# VC8Evrs3.net
KiCad netlist of a schematic drawn in EAGLE
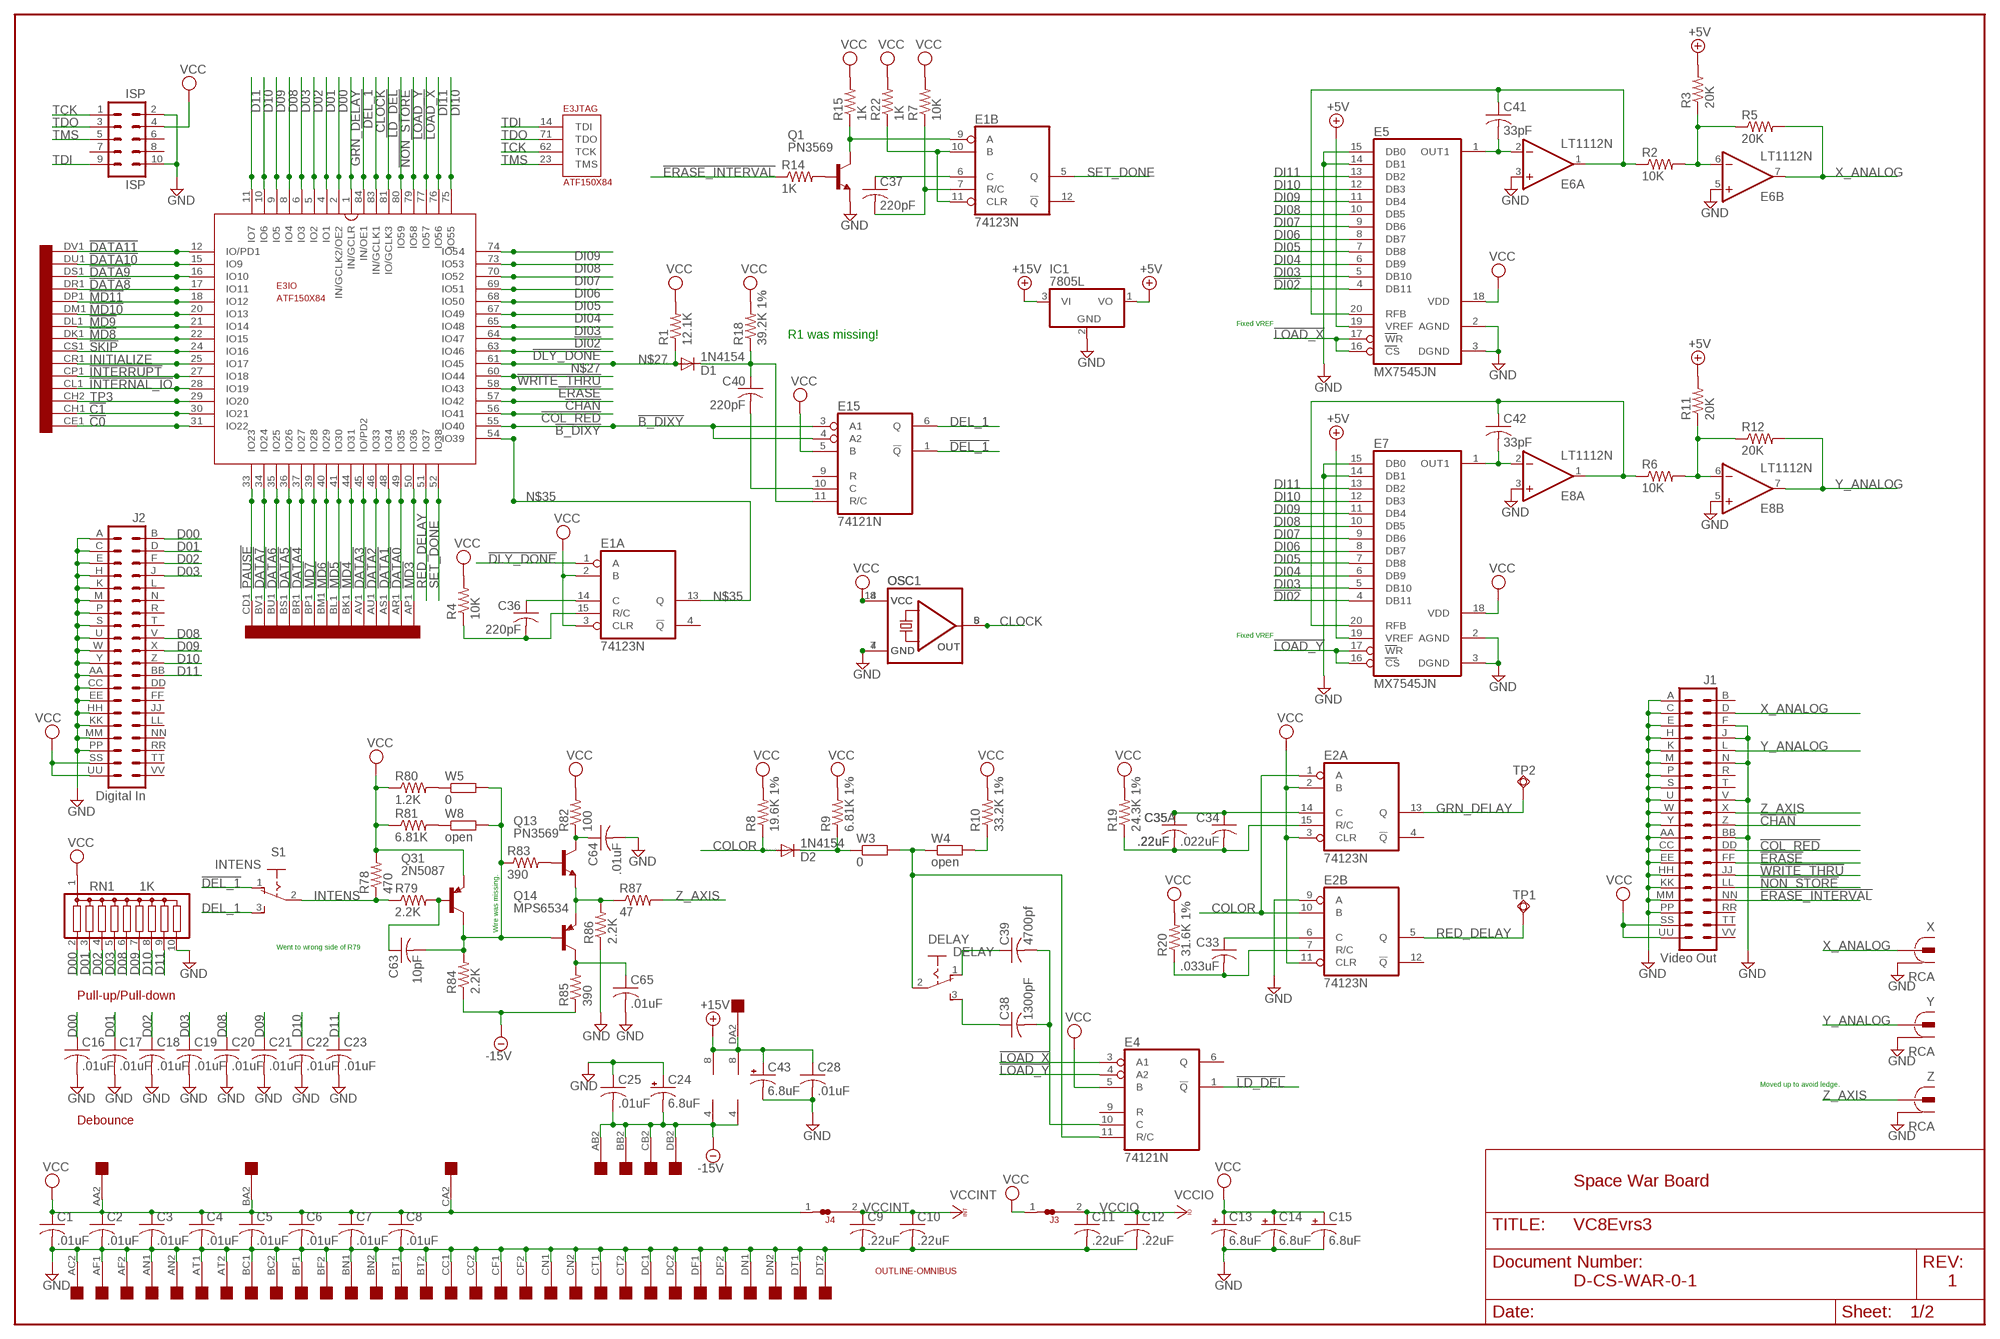
[diagram p0: schematic, sheet 1]

(export (version "E")
  (design (tool "Eeschema 10.0.6"))
  (components
    (comp (ref "C1")
      (value ".01uF")
      (footprint "eagle-import:C063-025X075")
      (libsource (lib "eagle-import") (part "C-US"))
    )
    (comp (ref "C2")
      (value ".01uF")
      (footprint "eagle-import:C063-025X075")
      (libsource (lib "eagle-import") (part "C-US"))
    )
    (comp (ref "C3")
      (value ".01uF")
      (footprint "eagle-import:C063-025X075")
      (libsource (lib "eagle-import") (part "C-US"))
    )
    (comp (ref "C4")
      (value ".01uF")
      (footprint "eagle-import:C063-025X075")
      (libsource (lib "eagle-import") (part "C-US"))
    )
    (comp (ref "C5")
      (value ".01uF")
      (footprint "eagle-import:C063-025X075")
      (libsource (lib "eagle-import") (part "C-US"))
    )
    (comp (ref "C6")
      (value ".01uF")
      (footprint "eagle-import:C063-025X075")
      (libsource (lib "eagle-import") (part "C-US"))
    )
    (comp (ref "C7")
      (value ".01uF")
      (footprint "eagle-import:C063-025X075")
      (libsource (lib "eagle-import") (part "C-US"))
    )
    (comp (ref "C8")
      (value ".01uF")
      (footprint "eagle-import:C063-025X075")
      (libsource (lib "eagle-import") (part "C-US"))
    )
    (comp (ref "C9")
      (value ".22uF")
      (footprint "eagle-import:C063-025X075")
      (libsource (lib "eagle-import") (part "C-US"))
    )
    (comp (ref "C10")
      (value ".22uF")
      (footprint "eagle-import:C063-025X075")
      (libsource (lib "eagle-import") (part "C-US"))
    )
    (comp (ref "C11")
      (value ".22uF")
      (footprint "eagle-import:C063-025X075")
      (libsource (lib "eagle-import") (part "C-US"))
    )
    (comp (ref "C12")
      (value ".22uF")
      (footprint "eagle-import:C063-025X075")
      (libsource (lib "eagle-import") (part "C-US"))
    )
    (comp (ref "C13")
      (value "6.8uF")
      (footprint "eagle-import:E12-8")
      (libsource (lib "eagle-import") (part "CPOL-USE20-8AXIAL"))
    )
    (comp (ref "C14")
      (value "6.8uF")
      (footprint "eagle-import:E12-8")
      (libsource (lib "eagle-import") (part "CPOL-USE20-8AXIAL"))
    )
    (comp (ref "C15")
      (value "6.8uF")
      (footprint "eagle-import:E12-8")
      (libsource (lib "eagle-import") (part "CPOL-USE20-8AXIAL"))
    )
    (comp (ref "C16")
      (value ".01uF")
      (footprint "eagle-import:C063-025X075")
      (libsource (lib "eagle-import") (part "C-US"))
    )
    (comp (ref "C17")
      (value ".01uF")
      (footprint "eagle-import:C063-025X075")
      (libsource (lib "eagle-import") (part "C-US"))
    )
    (comp (ref "C18")
      (value ".01uF")
      (footprint "eagle-import:C063-025X075")
      (libsource (lib "eagle-import") (part "C-US"))
    )
    (comp (ref "C19")
      (value ".01uF")
      (footprint "eagle-import:C063-025X075")
      (libsource (lib "eagle-import") (part "C-US"))
    )
    (comp (ref "C20")
      (value ".01uF")
      (footprint "eagle-import:C063-025X075")
      (libsource (lib "eagle-import") (part "C-US"))
    )
    (comp (ref "C21")
      (value ".01uF")
      (footprint "eagle-import:C063-025X075")
      (libsource (lib "eagle-import") (part "C-US"))
    )
    (comp (ref "C22")
      (value ".01uF")
      (footprint "eagle-import:C063-025X075")
      (libsource (lib "eagle-import") (part "C-US"))
    )
    (comp (ref "C23")
      (value ".01uF")
      (footprint "eagle-import:C063-025X075")
      (libsource (lib "eagle-import") (part "C-US"))
    )
    (comp (ref "C24")
      (value "6.8uF")
      (footprint "eagle-import:E12-8")
      (libsource (lib "eagle-import") (part "CPOL-USE20-8AXIAL"))
    )
    (comp (ref "C25")
      (value ".01uF")
      (footprint "eagle-import:C063-025X075")
      (libsource (lib "eagle-import") (part "C-US"))
    )
    (comp (ref "C28")
      (value ".01uF")
      (footprint "eagle-import:C063-025X075")
      (libsource (lib "eagle-import") (part "C-US"))
    )
    (comp (ref "C33")
      (value ".033uF")
      (footprint "eagle-import:C102-043X133")
      (libsource (lib "eagle-import") (part "C-US102-043X133"))
    )
    (comp (ref "C34")
      (value ".022uF")
      (footprint "eagle-import:C102-043X133")
      (libsource (lib "eagle-import") (part "C-US102-043X133"))
    )
    (comp (ref "C35")
      (value ".22uF")
      (footprint "eagle-import:C050-025X075")
      (libsource (lib "eagle-import") (part "C-US050-025X075"))
    )
    (comp (ref "C35A")
      (value ".22uF")
      (footprint "eagle-import:C102-043X133")
      (libsource (lib "eagle-import") (part "C-US102-043X133"))
    )
    (comp (ref "C36")
      (value "220pF")
      (footprint "eagle-import:C063-025X075")
      (libsource (lib "eagle-import") (part "C-US"))
    )
    (comp (ref "C37")
      (value "220pF")
      (footprint "eagle-import:C063-025X075")
      (libsource (lib "eagle-import") (part "C-US"))
    )
    (comp (ref "C38")
      (value "1300pF")
      (footprint "eagle-import:C150-054X183")
      (libsource (lib "eagle-import") (part "C-US150-054X183"))
    )
    (comp (ref "C39")
      (value "4700pf")
      (footprint "eagle-import:C102-043X133")
      (libsource (lib "eagle-import") (part "C-US102-043X133"))
    )
    (comp (ref "C40")
      (value "220pF")
      (footprint "eagle-import:C063-025X075")
      (libsource (lib "eagle-import") (part "C-US"))
    )
    (comp (ref "C41")
      (value "33pF")
      (footprint "eagle-import:C063-025X075")
      (libsource (lib "eagle-import") (part "C-US"))
    )
    (comp (ref "C42")
      (value "33pF")
      (footprint "eagle-import:C063-025X075")
      (libsource (lib "eagle-import") (part "C-US"))
    )
    (comp (ref "C43")
      (value "6.8uF")
      (footprint "eagle-import:E12-8")
      (libsource (lib "eagle-import") (part "CPOL-USE20-8AXIAL"))
    )
    (comp (ref "C63")
      (value "10pF")
      (footprint "eagle-import:C063-025X075")
      (libsource (lib "eagle-import") (part "C-US"))
    )
    (comp (ref "C64")
      (value ".01uF")
      (footprint "eagle-import:C063-025X075")
      (libsource (lib "eagle-import") (part "C-US"))
    )
    (comp (ref "C65")
      (value ".01uF")
      (footprint "eagle-import:C063-025X075")
      (libsource (lib "eagle-import") (part "C-US"))
    )
    (comp (ref "D1")
      (value "1N4154")
      (footprint "eagle-import:DO35-10")
      (libsource (lib "eagle-import") (part "DIODE-DO35-10"))
    )
    (comp (ref "D2")
      (value "1N4154")
      (footprint "eagle-import:DO35-10")
      (libsource (lib "eagle-import") (part "DIODE-DO35-10"))
    )
    (comp (ref "DELAY")
      (value "DELAY")
      (footprint "eagle-import:M251")
      (libsource (lib "eagle-import") (part "M251"))
    )
    (comp (ref "E1")
      (value "74123N")
      (footprint "eagle-import:DIL16")
      (libsource (lib "eagle-import") (part "74123N"))
    )
    (comp (ref "E2")
      (value "74123N")
      (footprint "eagle-import:DIL16")
      (libsource (lib "eagle-import") (part "74123N"))
    )
    (comp (ref "E3")
      (value "ATF150X84")
      (footprint "eagle-import:S84")
      (libsource (lib "eagle-import") (part "ATF150X84"))
    )
    (comp (ref "E4")
      (value "74121N")
      (footprint "eagle-import:DIL14")
      (libsource (lib "eagle-import") (part "74121N"))
    )
    (comp (ref "E5")
      (value "MX7545JN")
      (footprint "eagle-import:DIL20")
      (fields (field (name "MPN") "MX7545JN+"))
      (libsource (lib "eagle-import") (part "MX7545JN"))
    )
    (comp (ref "E6")
      (value "LT1112N")
      (footprint "eagle-import:DIL08")
      (libsource (lib "eagle-import") (part "1458NLM"))
    )
    (comp (ref "E7")
      (value "MX7545JN")
      (footprint "eagle-import:DIL20")
      (fields (field (name "MPN") "MX7545JN+"))
      (libsource (lib "eagle-import") (part "MX7545JN"))
    )
    (comp (ref "E8")
      (value "LT1112N")
      (footprint "eagle-import:DIL08")
      (libsource (lib "eagle-import") (part "1458NLM"))
    )
    (comp (ref "E15")
      (value "74121N")
      (footprint "eagle-import:DIL14")
      (libsource (lib "eagle-import") (part "74121N"))
    )
    (comp (ref "IC1")
      (value "7805L")
      (footprint "eagle-import:TO92")
      (libsource (lib "eagle-import") (part "78L05"))
    )
    (comp (ref "ISP")
      (value "ISP")
      (footprint "eagle-import:ML10")
      (libsource (lib "eagle-import") (part "ML10"))
    )
    (comp (ref "J1")
      (value "Video Out")
      (footprint "eagle-import:DEC40PINH")
      (libsource (lib "eagle-import") (part "DEC40PINH"))
    )
    (comp (ref "J2")
      (value "Digital In")
      (footprint "eagle-import:DEC40PINH")
      (libsource (lib "eagle-import") (part "DEC40PINH"))
    )
    (comp (ref "J3")
      (value "JUMPER-NC1")
      (footprint "eagle-import:NC1")
      (libsource (lib "eagle-import") (part "JUMPER-NC1"))
    )
    (comp (ref "J4")
      (value "JUMPER-NC1")
      (footprint "eagle-import:NC1")
      (libsource (lib "eagle-import") (part "JUMPER-NC1"))
    )
    (comp (ref "OMNIBUS")
      (value "QUAD")
      (footprint "eagle-import:EDGE-CON8")
      (libsource (lib "eagle-import") (part "QUAD"))
    )
    (comp (ref "OSC")
      (value "QG5460")
      (footprint "eagle-import:DIL08S")
      (libsource (lib "eagle-import") (part "QG5460"))
    )
    (comp (ref "OSC1")
      (value "QG5860")
      (footprint "eagle-import:DIL14S")
      (libsource (lib "eagle-import") (part "QG5860"))
    )
    (comp (ref "Q1")
      (value "PN3569")
      (footprint "eagle-import:TO5")
      (libsource (lib "eagle-import") (part "-NPN-TO5"))
    )
    (comp (ref "Q13")
      (value "PN3569")
      (footprint "eagle-import:TO5")
      (libsource (lib "eagle-import") (part "-NPN-TO5"))
    )
    (comp (ref "Q14")
      (value "MPS6534")
      (footprint "eagle-import:TO5")
      (libsource (lib "eagle-import") (part "-PNP-TO5"))
    )
    (comp (ref "Q31")
      (value "2N5087")
      (footprint "eagle-import:TO5")
      (libsource (lib "eagle-import") (part "-PNP-TO5"))
    )
    (comp (ref "R1")
      (value "12.1K")
      (footprint "eagle-import:0207_15")
      (libsource (lib "eagle-import") (part "R-US_0207/15"))
    )
    (comp (ref "R2")
      (value "10K")
      (footprint "eagle-import:0207_10")
      (libsource (lib "eagle-import") (part "R-US_0207/10"))
    )
    (comp (ref "R3")
      (value "20K")
      (footprint "eagle-import:0207_10")
      (libsource (lib "eagle-import") (part "R-US_0207/10"))
    )
    (comp (ref "R4")
      (value "10K")
      (footprint "eagle-import:0207_10")
      (libsource (lib "eagle-import") (part "R-US_0207/10"))
    )
    (comp (ref "R5")
      (value "20K")
      (footprint "eagle-import:0207_10")
      (libsource (lib "eagle-import") (part "R-US_0207/10"))
    )
    (comp (ref "R6")
      (value "10K")
      (footprint "eagle-import:0207_10")
      (libsource (lib "eagle-import") (part "R-US_0207/10"))
    )
    (comp (ref "R7")
      (value "10K")
      (footprint "eagle-import:0207_10")
      (libsource (lib "eagle-import") (part "R-US_0207/10"))
    )
    (comp (ref "R8")
      (value "19.6K 1%")
      (footprint "eagle-import:0207_15")
      (libsource (lib "eagle-import") (part "R-US_0207/15"))
    )
    (comp (ref "R9")
      (value "6.81K 1%")
      (footprint "eagle-import:0207_15")
      (libsource (lib "eagle-import") (part "R-US_0207/15"))
    )
    (comp (ref "R10")
      (value "33.2K 1%")
      (footprint "eagle-import:0207_15")
      (libsource (lib "eagle-import") (part "R-US_0207/15"))
    )
    (comp (ref "R11")
      (value "20K")
      (footprint "eagle-import:0207_10")
      (libsource (lib "eagle-import") (part "R-US_0207/10"))
    )
    (comp (ref "R12")
      (value "20K")
      (footprint "eagle-import:0207_10")
      (libsource (lib "eagle-import") (part "R-US_0207/10"))
    )
    (comp (ref "R14")
      (value "1K")
      (footprint "eagle-import:0207_10")
      (libsource (lib "eagle-import") (part "R-US_0207/10"))
    )
    (comp (ref "R15")
      (value "1K")
      (footprint "eagle-import:0207_10")
      (libsource (lib "eagle-import") (part "R-US_0207/10"))
    )
    (comp (ref "R18")
      (value "39.2K 1%")
      (footprint "eagle-import:0207_15")
      (libsource (lib "eagle-import") (part "R-US_0207/15"))
    )
    (comp (ref "R19")
      (value "24.3K 1%")
      (footprint "eagle-import:0207_15")
      (libsource (lib "eagle-import") (part "R-US_0207/15"))
    )
    (comp (ref "R20")
      (value "31.6K 1%")
      (footprint "eagle-import:0207_15")
      (libsource (lib "eagle-import") (part "R-US_0207/15"))
    )
    (comp (ref "R22")
      (value "1K")
      (footprint "eagle-import:0207_10")
      (libsource (lib "eagle-import") (part "R-US_0207/10"))
    )
    (comp (ref "R78")
      (value "470")
      (footprint "eagle-import:0207_10")
      (libsource (lib "eagle-import") (part "R-US_0207/10"))
    )
    (comp (ref "R79")
      (value "2.2K")
      (footprint "eagle-import:0207_10")
      (libsource (lib "eagle-import") (part "R-US_0207/10"))
    )
    (comp (ref "R80")
      (value "1.2K")
      (footprint "eagle-import:0207_10")
      (libsource (lib "eagle-import") (part "R-US_0207/10"))
    )
    (comp (ref "R81")
      (value "6.81K")
      (footprint "eagle-import:0207_10")
      (libsource (lib "eagle-import") (part "R-US_0207/10"))
    )
    (comp (ref "R82")
      (value "100")
      (footprint "eagle-import:0207_10")
      (libsource (lib "eagle-import") (part "R-US_0207/10"))
    )
    (comp (ref "R83")
      (value "390")
      (footprint "eagle-import:0207_10")
      (libsource (lib "eagle-import") (part "R-US_0207/10"))
    )
    (comp (ref "R84")
      (value "2.2K")
      (footprint "eagle-import:0207_10")
      (libsource (lib "eagle-import") (part "R-US_0207/10"))
    )
    (comp (ref "R85")
      (value "390")
      (footprint "eagle-import:0207_10")
      (libsource (lib "eagle-import") (part "R-US_0207/10"))
    )
    (comp (ref "R86")
      (value "2.2K")
      (footprint "eagle-import:0207_10")
      (libsource (lib "eagle-import") (part "R-US_0207/10"))
    )
    (comp (ref "R87")
      (value "47")
      (footprint "eagle-import:0207_10")
      (libsource (lib "eagle-import") (part "R-US_0207/10"))
    )
    (comp (ref "RN1")
      (value "1K")
      (footprint "eagle-import:SIL10")
      (libsource (lib "eagle-import") (part "G09R"))
    )
    (comp (ref "S1")
      (value "INTENS")
      (footprint "eagle-import:M251")
      (libsource (lib "eagle-import") (part "M251"))
    )
    (comp (ref "TP1")
      (value "TPSQPAD1-17")
      (footprint "eagle-import:P1-17")
      (libsource (lib "eagle-import") (part "TPSQPAD1-17"))
    )
    (comp (ref "TP2")
      (value "TPSQPAD1-17")
      (footprint "eagle-import:P1-17")
      (libsource (lib "eagle-import") (part "TPSQPAD1-17"))
    )
    (comp (ref "U$1")
      (value "OUTLINE-OMNIBUS")
      (footprint "eagle-import:OMNIBUS")
      (libsource (lib "eagle-import") (part "OUTLINE-OMNIBUS"))
    )
    (comp (ref "W3")
      (value "0")
      (footprint "eagle-import:0207_10")
      (libsource (lib "eagle-import") (part "R-EU_0207/10"))
    )
    (comp (ref "W4")
      (value "open")
      (footprint "eagle-import:0207_10")
      (libsource (lib "eagle-import") (part "R-EU_0207/10"))
    )
    (comp (ref "W5")
      (value "0")
      (footprint "eagle-import:0207_10")
      (libsource (lib "eagle-import") (part "R-EU_0207/10"))
    )
    (comp (ref "W8")
      (value "open")
      (footprint "eagle-import:0207_10")
      (libsource (lib "eagle-import") (part "R-EU_0207/10"))
    )
    (comp (ref "X")
      (value "RCA")
      (footprint "eagle-import:RCA")
      (libsource (lib "eagle-import") (part "RCA"))
    )
    (comp (ref "Y")
      (value "RCA")
      (footprint "eagle-import:RCA")
      (libsource (lib "eagle-import") (part "RCA"))
    )
    (comp (ref "Z")
      (value "RCA")
      (footprint "eagle-import:RCA")
      (libsource (lib "eagle-import") (part "RCA"))
    )
  )
  (nets
    (net (code "1") (name "+5V") (class "Default")
      (node (ref "E5") (pin "19") (pinfunction "VREF_19") (pintype "input"))
      (node (ref "E7") (pin "19") (pinfunction "VREF_19") (pintype "input"))
      (node (ref "IC1") (pin "1") (pinfunction "VO_1") (pintype "passive"))
      (node (ref "R11") (pin "2") (pinfunction "2_2") (pintype "passive"))
      (node (ref "R3") (pin "2") (pinfunction "2_2") (pintype "passive"))
    )
    (net (code "2") (name "+15V") (class "Default")
      (node (ref "C28") (pin "1") (pinfunction "1_1") (pintype "passive"))
      (node (ref "C43") (pin "+") (pinfunction "+_+") (pintype "passive"))
      (node (ref "E6") (pin "8") (pinfunction "V+_8") (pintype "power_in"))
      (node (ref "E8") (pin "8") (pinfunction "V+_8") (pintype "power_in"))
      (node (ref "IC1") (pin "3") (pinfunction "VI_3") (pintype "input"))
      (node (ref "OMNIBUS") (pin "DA2") (pinfunction "1_DA2") (pintype "bidirectional"))
    )
    (net (code "3") (name "-15V") (class "Default")
      (node (ref "C24") (pin "-") (pinfunction "-_-") (pintype "passive"))
      (node (ref "C25") (pin "2") (pinfunction "2_2") (pintype "passive"))
      (node (ref "E6") (pin "4") (pinfunction "V-_4") (pintype "power_in"))
      (node (ref "E8") (pin "4") (pinfunction "V-_4") (pintype "power_in"))
      (node (ref "OMNIBUS") (pin "AB2") (pinfunction "1_AB2") (pintype "bidirectional"))
      (node (ref "OMNIBUS") (pin "BB2") (pinfunction "1_BB2") (pintype "bidirectional"))
      (node (ref "OMNIBUS") (pin "CB2") (pinfunction "1_CB2") (pintype "bidirectional"))
      (node (ref "OMNIBUS") (pin "DB2") (pinfunction "1_DB2") (pintype "bidirectional"))
      (node (ref "R84") (pin "1") (pinfunction "1_1") (pintype "passive"))
      (node (ref "R85") (pin "1") (pinfunction "1_1") (pintype "passive"))
    )
    (net (code "4") (name "CLOCK") (class "Default")
      (node (ref "E3") (pin "83") (pinfunction "IN/GCLK1_83") (pintype "input"))
      (node (ref "OSC") (pin "5") (pinfunction "OUT_5") (pintype "output"))
      (node (ref "OSC1") (pin "8") (pinfunction "OUT_8") (pintype "output"))
    )
    (net (code "5") (name "COLOR") (class "Default")
      (node (ref "D2") (pin "A") (pinfunction "A_A") (pintype "passive"))
      (node (ref "E2") (pin "1") (pinfunction "A_1") (pintype "input"))
      (node (ref "E2") (pin "10") (pinfunction "B_10") (pintype "input"))
      (node (ref "R8") (pin "1") (pinfunction "1_1") (pintype "passive"))
    )
    (net (code "6") (name "D00") (class "Default")
      (node (ref "C16") (pin "1") (pinfunction "1_1") (pintype "passive"))
      (node (ref "E3") (pin "2") (pinfunction "IN/GCLK2/OE2_2") (pintype "input"))
      (node (ref "J2") (pin "B") (pinfunction "2_B") (pintype "bidirectional"))
      (node (ref "RN1") (pin "2") (pinfunction "2_2") (pintype "passive"))
    )
    (net (code "7") (name "D01") (class "Default")
      (node (ref "C17") (pin "1") (pinfunction "1_1") (pintype "passive"))
      (node (ref "E3") (pin "4") (pinfunction "IO1_4") (pintype "bidirectional"))
      (node (ref "J2") (pin "D") (pinfunction "4_D") (pintype "bidirectional"))
      (node (ref "RN1") (pin "3") (pinfunction "3_3") (pintype "passive"))
    )
    (net (code "8") (name "D02") (class "Default")
      (node (ref "C18") (pin "1") (pinfunction "1_1") (pintype "passive"))
      (node (ref "E3") (pin "5") (pinfunction "IO2_5") (pintype "bidirectional"))
      (node (ref "J2") (pin "F") (pinfunction "6_F") (pintype "bidirectional"))
      (node (ref "RN1") (pin "4") (pinfunction "4_4") (pintype "passive"))
    )
    (net (code "9") (name "D03") (class "Default")
      (node (ref "C19") (pin "1") (pinfunction "1_1") (pintype "passive"))
      (node (ref "E3") (pin "6") (pinfunction "IO3_6") (pintype "bidirectional"))
      (node (ref "J2") (pin "J") (pinfunction "8_J") (pintype "bidirectional"))
      (node (ref "RN1") (pin "5") (pinfunction "5_5") (pintype "passive"))
    )
    (net (code "10") (name "D08") (class "Default")
      (node (ref "C20") (pin "1") (pinfunction "1_1") (pintype "passive"))
      (node (ref "E3") (pin "8") (pinfunction "IO4_8") (pintype "bidirectional"))
      (node (ref "J2") (pin "V") (pinfunction "18_V") (pintype "bidirectional"))
      (node (ref "RN1") (pin "6") (pinfunction "6_6") (pintype "passive"))
    )
    (net (code "11") (name "D09") (class "Default")
      (node (ref "C21") (pin "1") (pinfunction "1_1") (pintype "passive"))
      (node (ref "E3") (pin "9") (pinfunction "IO5_9") (pintype "bidirectional"))
      (node (ref "J2") (pin "X") (pinfunction "20_X") (pintype "bidirectional"))
      (node (ref "RN1") (pin "7") (pinfunction "7_7") (pintype "passive"))
    )
    (net (code "12") (name "D10") (class "Default")
      (node (ref "C22") (pin "1") (pinfunction "1_1") (pintype "passive"))
      (node (ref "E3") (pin "10") (pinfunction "IO6_10") (pintype "bidirectional"))
      (node (ref "J2") (pin "Z") (pinfunction "22_Z") (pintype "bidirectional"))
      (node (ref "RN1") (pin "8") (pinfunction "8_8") (pintype "passive"))
    )
    (net (code "13") (name "D11") (class "Default")
      (node (ref "C23") (pin "1") (pinfunction "1_1") (pintype "passive"))
      (node (ref "E3") (pin "11") (pinfunction "IO7_11") (pintype "bidirectional"))
      (node (ref "J2") (pin "BB") (pinfunction "24_BB") (pintype "bidirectional"))
      (node (ref "RN1") (pin "9") (pinfunction "9_9") (pintype "passive"))
    )
    (net (code "14") (name "DEL_1") (class "Default")
      (node (ref "E15") (pin "6") (pinfunction "Q_6") (pintype "output"))
      (node (ref "S1") (pin "3") (pinfunction "S_3") (pintype "passive"))
    )
    (net (code "15") (name "DI03") (class "Default")
      (node (ref "E3") (pin "65") (pinfunction "IO48_65") (pintype "bidirectional"))
      (node (ref "E5") (pin "5") (pinfunction "DB10_5") (pintype "input"))
      (node (ref "E7") (pin "5") (pinfunction "DB10_5") (pintype "input"))
    )
    (net (code "16") (name "DI04") (class "Default")
      (node (ref "E3") (pin "67") (pinfunction "IO49_67") (pintype "bidirectional"))
      (node (ref "E5") (pin "6") (pinfunction "DB9_6") (pintype "input"))
      (node (ref "E7") (pin "6") (pinfunction "DB9_6") (pintype "input"))
    )
    (net (code "17") (name "DI05") (class "Default")
      (node (ref "E3") (pin "68") (pinfunction "IO50_68") (pintype "bidirectional"))
      (node (ref "E5") (pin "7") (pinfunction "DB8_7") (pintype "input"))
      (node (ref "E7") (pin "7") (pinfunction "DB8_7") (pintype "input"))
    )
    (net (code "18") (name "DI06") (class "Default")
      (node (ref "E3") (pin "69") (pinfunction "IO51_69") (pintype "bidirectional"))
      (node (ref "E5") (pin "8") (pinfunction "DB7_8") (pintype "input"))
      (node (ref "E7") (pin "8") (pinfunction "DB7_8") (pintype "input"))
    )
    (net (code "19") (name "DI07") (class "Default")
      (node (ref "E3") (pin "70") (pinfunction "IO52_70") (pintype "bidirectional"))
      (node (ref "E5") (pin "9") (pinfunction "DB6_9") (pintype "input"))
      (node (ref "E7") (pin "9") (pinfunction "DB6_9") (pintype "input"))
    )
    (net (code "20") (name "DI08") (class "Default")
      (node (ref "E3") (pin "73") (pinfunction "IO53_73") (pintype "bidirectional"))
      (node (ref "E5") (pin "10") (pinfunction "DB5_10") (pintype "input"))
      (node (ref "E7") (pin "10") (pinfunction "DB5_10") (pintype "input"))
    )
    (net (code "21") (name "DI09") (class "Default")
      (node (ref "E3") (pin "74") (pinfunction "IO54_74") (pintype "bidirectional"))
      (node (ref "E5") (pin "11") (pinfunction "DB4_11") (pintype "input"))
      (node (ref "E7") (pin "11") (pinfunction "DB4_11") (pintype "input"))
    )
    (net (code "22") (name "DI10") (class "Default")
      (node (ref "E3") (pin "75") (pinfunction "IO55_75") (pintype "bidirectional"))
      (node (ref "E5") (pin "12") (pinfunction "DB3_12") (pintype "input"))
      (node (ref "E7") (pin "12") (pinfunction "DB3_12") (pintype "input"))
    )
    (net (code "23") (name "DI11") (class "Default")
      (node (ref "E3") (pin "76") (pinfunction "IO56_76") (pintype "bidirectional"))
      (node (ref "E5") (pin "13") (pinfunction "DB2_13") (pintype "input"))
      (node (ref "E7") (pin "13") (pinfunction "DB2_13") (pintype "input"))
    )
    (net (code "24") (name "GND") (class "Default")
      (node (ref "C1") (pin "2") (pinfunction "2_2") (pintype "passive"))
      (node (ref "C10") (pin "2") (pinfunction "2_2") (pintype "passive"))
      (node (ref "C11") (pin "2") (pinfunction "2_2") (pintype "passive"))
      (node (ref "C12") (pin "2") (pinfunction "2_2") (pintype "passive"))
      (node (ref "C13") (pin "-") (pinfunction "-_-") (pintype "passive"))
      (node (ref "C14") (pin "-") (pinfunction "-_-") (pintype "passive"))
      (node (ref "C15") (pin "-") (pinfunction "-_-") (pintype "passive"))
      (node (ref "C16") (pin "2") (pinfunction "2_2") (pintype "passive"))
      (node (ref "C17") (pin "2") (pinfunction "2_2") (pintype "passive"))
      (node (ref "C18") (pin "2") (pinfunction "2_2") (pintype "passive"))
      (node (ref "C19") (pin "2") (pinfunction "2_2") (pintype "passive"))
      (node (ref "C2") (pin "2") (pinfunction "2_2") (pintype "passive"))
      (node (ref "C20") (pin "2") (pinfunction "2_2") (pintype "passive"))
      (node (ref "C21") (pin "2") (pinfunction "2_2") (pintype "passive"))
      (node (ref "C22") (pin "2") (pinfunction "2_2") (pintype "passive"))
      (node (ref "C23") (pin "2") (pinfunction "2_2") (pintype "passive"))
      (node (ref "C24") (pin "+") (pinfunction "+_+") (pintype "passive"))
      (node (ref "C25") (pin "1") (pinfunction "1_1") (pintype "passive"))
      (node (ref "C28") (pin "2") (pinfunction "2_2") (pintype "passive"))
      (node (ref "C3") (pin "2") (pinfunction "2_2") (pintype "passive"))
      (node (ref "C4") (pin "2") (pinfunction "2_2") (pintype "passive"))
      (node (ref "C43") (pin "-") (pinfunction "-_-") (pintype "passive"))
      (node (ref "C5") (pin "2") (pinfunction "2_2") (pintype "passive"))
      (node (ref "C6") (pin "2") (pinfunction "2_2") (pintype "passive"))
      (node (ref "C64") (pin "2") (pinfunction "2_2") (pintype "passive"))
      (node (ref "C65") (pin "2") (pinfunction "2_2") (pintype "passive"))
      (node (ref "C7") (pin "2") (pinfunction "2_2") (pintype "passive"))
      (node (ref "C8") (pin "2") (pinfunction "2_2") (pintype "passive"))
      (node (ref "C9") (pin "2") (pinfunction "2_2") (pintype "passive"))
      (node (ref "E2") (pin "9") (pinfunction "A_9") (pintype "input"))
      (node (ref "E5") (pin "14") (pinfunction "DB1_14") (pintype "input"))
      (node (ref "E5") (pin "15") (pinfunction "DB0_15") (pintype "input"))
      (node (ref "E5") (pin "2") (pinfunction "AGND_2") (pintype "power_in"))
      (node (ref "E5") (pin "3") (pinfunction "DGND_3") (pintype "power_in"))
      (node (ref "E6") (pin "3") (pinfunction "+IN_3") (pintype "input"))
      (node (ref "E6") (pin "5") (pinfunction "+IN_5") (pintype "input"))
      (node (ref "E7") (pin "14") (pinfunction "DB1_14") (pintype "input"))
      (node (ref "E7") (pin "15") (pinfunction "DB0_15") (pintype "input"))
      (node (ref "E7") (pin "2") (pinfunction "AGND_2") (pintype "power_in"))
      (node (ref "E7") (pin "3") (pinfunction "DGND_3") (pintype "power_in"))
      (node (ref "E8") (pin "3") (pinfunction "+IN_3") (pintype "input"))
      (node (ref "E8") (pin "5") (pinfunction "+IN_5") (pintype "input"))
      (node (ref "IC1") (pin "2") (pinfunction "GND_2") (pintype "passive"))
      (node (ref "ISP") (pin "10") (pinfunction "10_10") (pintype "passive"))
      (node (ref "ISP") (pin "2") (pinfunction "2_2") (pintype "passive"))
      (node (ref "J1") (pin "A") (pinfunction "1_A") (pintype "bidirectional"))
      (node (ref "J1") (pin "AA") (pinfunction "23_AA") (pintype "bidirectional"))
      (node (ref "J1") (pin "BB") (pinfunction "24_BB") (pintype "bidirectional"))
      (node (ref "J1") (pin "C") (pinfunction "3_C") (pintype "bidirectional"))
      (node (ref "J1") (pin "CC") (pinfunction "25_CC") (pintype "bidirectional"))
      (node (ref "J1") (pin "E") (pinfunction "5_E") (pintype "bidirectional"))
      (node (ref "J1") (pin "EE") (pinfunction "27_EE") (pintype "bidirectional"))
      (node (ref "J1") (pin "F") (pinfunction "6_F") (pintype "bidirectional"))
      (node (ref "J1") (pin "H") (pinfunction "7_H") (pintype "bidirectional"))
      (node (ref "J1") (pin "HH") (pinfunction "29_HH") (pintype "bidirectional"))
      (node (ref "J1") (pin "J") (pinfunction "8_J") (pintype "bidirectional"))
      (node (ref "J1") (pin "K") (pinfunction "9_K") (pintype "bidirectional"))
      (node (ref "J1") (pin "KK") (pinfunction "31_KK") (pintype "bidirectional"))
      (node (ref "J1") (pin "M") (pinfunction "11_M") (pintype "bidirectional"))
      (node (ref "J1") (pin "MM") (pinfunction "33_MM") (pintype "bidirectional"))
      (node (ref "J1") (pin "N") (pinfunction "12_N") (pintype "bidirectional"))
      (node (ref "J1") (pin "P") (pinfunction "13_P") (pintype "bidirectional"))
      (node (ref "J1") (pin "PP") (pinfunction "35_PP") (pintype "bidirectional"))
      (node (ref "J1") (pin "S") (pinfunction "15_S") (pintype "bidirectional"))
      (node (ref "J1") (pin "U") (pinfunction "17_U") (pintype "bidirectional"))
      (node (ref "J1") (pin "V") (pinfunction "18_V") (pintype "bidirectional"))
      (node (ref "J1") (pin "W") (pinfunction "19_W") (pintype "bidirectional"))
      (node (ref "J1") (pin "Y") (pinfunction "21_Y") (pintype "bidirectional"))
      (node (ref "J2") (pin "A") (pinfunction "1_A") (pintype "bidirectional"))
      (node (ref "J2") (pin "AA") (pinfunction "23_AA") (pintype "bidirectional"))
      (node (ref "J2") (pin "C") (pinfunction "3_C") (pintype "bidirectional"))
      (node (ref "J2") (pin "CC") (pinfunction "25_CC") (pintype "bidirectional"))
      (node (ref "J2") (pin "E") (pinfunction "5_E") (pintype "bidirectional"))
      (node (ref "J2") (pin "EE") (pinfunction "27_EE") (pintype "bidirectional"))
      (node (ref "J2") (pin "H") (pinfunction "7_H") (pintype "bidirectional"))
      (node (ref "J2") (pin "HH") (pinfunction "29_HH") (pintype "bidirectional"))
      (node (ref "J2") (pin "K") (pinfunction "9_K") (pintype "bidirectional"))
      (node (ref "J2") (pin "KK") (pinfunction "31_KK") (pintype "bidirectional"))
      (node (ref "J2") (pin "M") (pinfunction "11_M") (pintype "bidirectional"))
      (node (ref "J2") (pin "MM") (pinfunction "33_MM") (pintype "bidirectional"))
      (node (ref "J2") (pin "P") (pinfunction "13_P") (pintype "bidirectional"))
      (node (ref "J2") (pin "PP") (pinfunction "35_PP") (pintype "bidirectional"))
      (node (ref "J2") (pin "S") (pinfunction "15_S") (pintype "bidirectional"))
      (node (ref "J2") (pin "U") (pinfunction "17_U") (pintype "bidirectional"))
      (node (ref "J2") (pin "W") (pinfunction "19_W") (pintype "bidirectional"))
      (node (ref "J2") (pin "Y") (pinfunction "21_Y") (pintype "bidirectional"))
      (node (ref "OMNIBUS") (pin "AC2") (pinfunction "1_AC2") (pintype "bidirectional"))
      (node (ref "OMNIBUS") (pin "AF1") (pinfunction "1_AF1") (pintype "bidirectional"))
      (node (ref "OMNIBUS") (pin "AF2") (pinfunction "1_AF2") (pintype "bidirectional"))
      (node (ref "OMNIBUS") (pin "AN1") (pinfunction "1_AN1") (pintype "bidirectional"))
      (node (ref "OMNIBUS") (pin "AN2") (pinfunction "1_AN2") (pintype "bidirectional"))
      (node (ref "OMNIBUS") (pin "AT1") (pinfunction "1_AT1") (pintype "bidirectional"))
      (node (ref "OMNIBUS") (pin "AT2") (pinfunction "1_AT2") (pintype "bidirectional"))
      (node (ref "OMNIBUS") (pin "BC1") (pinfunction "1_BC1") (pintype "bidirectional"))
      (node (ref "OMNIBUS") (pin "BC2") (pinfunction "1_BC2") (pintype "bidirectional"))
      (node (ref "OMNIBUS") (pin "BF1") (pinfunction "1_BF1") (pintype "bidirectional"))
      (node (ref "OMNIBUS") (pin "BF2") (pinfunction "1_BF2") (pintype "bidirectional"))
      (node (ref "OMNIBUS") (pin "BN1") (pinfunction "1_BN1") (pintype "bidirectional"))
      (node (ref "OMNIBUS") (pin "BN2") (pinfunction "1_BN2") (pintype "bidirectional"))
      (node (ref "OMNIBUS") (pin "BT1") (pinfunction "1_BT1") (pintype "bidirectional"))
      (node (ref "OMNIBUS") (pin "BT2") (pinfunction "1_BT2") (pintype "bidirectional"))
      (node (ref "OMNIBUS") (pin "CC1") (pinfunction "1_CC1") (pintype "bidirectional"))
      (node (ref "OMNIBUS") (pin "CC2") (pinfunction "1_CC2") (pintype "bidirectional"))
      (node (ref "OMNIBUS") (pin "CF1") (pinfunction "1_CF1") (pintype "bidirectional"))
      (node (ref "OMNIBUS") (pin "CF2") (pinfunction "1_CF2") (pintype "bidirectional"))
      (node (ref "OMNIBUS") (pin "CN1") (pinfunction "1_CN1") (pintype "bidirectional"))
      (node (ref "OMNIBUS") (pin "CN2") (pinfunction "1_CN2") (pintype "bidirectional"))
      (node (ref "OMNIBUS") (pin "CT1") (pinfunction "1_CT1") (pintype "bidirectional"))
      (node (ref "OMNIBUS") (pin "CT2") (pinfunction "1_CT2") (pintype "bidirectional"))
      (node (ref "OMNIBUS") (pin "DC1") (pinfunction "1_DC1") (pintype "bidirectional"))
      (node (ref "OMNIBUS") (pin "DC2") (pinfunction "1_DC2") (pintype "bidirectional"))
      (node (ref "OMNIBUS") (pin "DF1") (pinfunction "1_DF1") (pintype "bidirectional"))
      (node (ref "OMNIBUS") (pin "DF2") (pinfunction "1_DF2") (pintype "bidirectional"))
      (node (ref "OMNIBUS") (pin "DN1") (pinfunction "1_DN1") (pintype "bidirectional"))
      (node (ref "OMNIBUS") (pin "DN2") (pinfunction "1_DN2") (pintype "bidirectional"))
      (node (ref "OMNIBUS") (pin "DT1") (pinfunction "1_DT1") (pintype "bidirectional"))
      (node (ref "OMNIBUS") (pin "DT2") (pinfunction "1_DT2") (pintype "bidirectional"))
      (node (ref "OSC") (pin "4") (pinfunction "GND_4") (pintype "power_in"))
      (node (ref "OSC1") (pin "7") (pinfunction "GND_7") (pintype "power_in"))
      (node (ref "Q1") (pin "1") (pinfunction "E_1") (pintype "passive"))
      (node (ref "R86") (pin "1") (pinfunction "1_1") (pintype "passive"))
      (node (ref "RN1") (pin "10") (pinfunction "10_10") (pintype "passive"))
      (node (ref "X") (pin "1") (pinfunction "1_1") (pintype "passive"))
      (node (ref "X") (pin "1@1") (pinfunction "1_1@1") (pintype "passive"))
      (node (ref "X") (pin "1@2") (pinfunction "1_1@2") (pintype "passive"))
      (node (ref "Y") (pin "1") (pinfunction "1_1") (pintype "passive"))
      (node (ref "Y") (pin "1@1") (pinfunction "1_1@1") (pintype "passive"))
      (node (ref "Y") (pin "1@2") (pinfunction "1_1@2") (pintype "passive"))
      (node (ref "Z") (pin "1") (pinfunction "1_1") (pintype "passive"))
      (node (ref "Z") (pin "1@1") (pinfunction "1_1@1") (pintype "passive"))
      (node (ref "Z") (pin "1@2") (pinfunction "1_1@2") (pintype "passive"))
    )
    (net (code "25") (name "GRN_DELAY") (class "Default")
      (node (ref "E2") (pin "13") (pinfunction "Q_13") (pintype "output"))
      (node (ref "E3") (pin "1") (pinfunction "IN/GCLR_1") (pintype "input"))
      (node (ref "TP2") (pin "TP") (pinfunction "TP_TP") (pintype "input"))
    )
    (net (code "26") (name "INITIALIZE") (class "Default")
      (node (ref "E3") (pin "25") (pinfunction "IO17_25") (pintype "bidirectional"))
      (node (ref "OMNIBUS") (pin "CR1") (pinfunction "1_CR1") (pintype "bidirectional"))
    )
    (net (code "27") (name "INTENS") (class "Default")
      (node (ref "R78") (pin "1") (pinfunction "1_1") (pintype "passive"))
      (node (ref "R79") (pin "1") (pinfunction "1_1") (pintype "passive"))
      (node (ref "S1") (pin "2") (pinfunction "P_2") (pintype "passive"))
    )
    (net (code "28") (name "N$27") (class "Default")
      (node (ref "D1") (pin "A") (pinfunction "A_A") (pintype "passive"))
      (node (ref "E3") (pin "61") (pinfunction "IO45_61") (pintype "bidirectional"))
      (node (ref "R1") (pin "1") (pinfunction "1_1") (pintype "passive"))
    )
    (net (code "29") (name "N$35") (class "Default")
      (node (ref "E1") (pin "13") (pinfunction "Q_13") (pintype "output"))
      (node (ref "E3") (pin "54") (pinfunction "IO39_54") (pintype "bidirectional"))
    )
    (net (code "30") (name "Net-(D2-PadC)") (class "Default")
      (node (ref "D2") (pin "C") (pinfunction "C_C") (pintype "passive"))
      (node (ref "R9") (pin "1") (pinfunction "1_1") (pintype "passive"))
      (node (ref "W3") (pin "1") (pinfunction "1_1") (pintype "passive"))
    )
    (net (code "31") (name "Net-(DELAY-O)") (class "Default")
      (node (ref "C39") (pin "1") (pinfunction "1_1") (pintype "passive"))
      (node (ref "DELAY") (pin "1") (pinfunction "O_1") (pintype "passive"))
    )
    (net (code "32") (name "Net-(DELAY-P)") (class "Default")
      (node (ref "DELAY") (pin "2") (pinfunction "P_2") (pintype "passive"))
      (node (ref "E4") (pin "11") (pinfunction "R/C_11") (pintype "input"))
      (node (ref "W3") (pin "2") (pinfunction "2_2") (pintype "passive"))
      (node (ref "W4") (pin "1") (pinfunction "1_1") (pintype "passive"))
    )
    (net (code "33") (name "Net-(DELAY-S)") (class "Default")
      (node (ref "C38") (pin "1") (pinfunction "1_1") (pintype "passive"))
      (node (ref "DELAY") (pin "3") (pinfunction "S_3") (pintype "passive"))
    )
    (net (code "34") (name "Net-(E1A-C)") (class "Default")
      (node (ref "C36") (pin "1") (pinfunction "1_1") (pintype "passive"))
      (node (ref "E1") (pin "14") (pinfunction "C_14") (pintype "input"))
    )
    (net (code "35") (name "Net-(E1A-R{slash}C)") (class "Default")
      (node (ref "C36") (pin "2") (pinfunction "2_2") (pintype "passive"))
      (node (ref "E1") (pin "15") (pinfunction "R/C_15") (pintype "input"))
      (node (ref "R4") (pin "1") (pinfunction "1_1") (pintype "passive"))
    )
    (net (code "36") (name "Net-(E1B-A)") (class "Default")
      (node (ref "E1") (pin "9") (pinfunction "A_9") (pintype "input"))
      (node (ref "Q1") (pin "3") (pinfunction "C_3") (pintype "passive"))
      (node (ref "R15") (pin "1") (pinfunction "1_1") (pintype "passive"))
    )
    (net (code "37") (name "Net-(E1B-B)") (class "Default")
      (node (ref "E1") (pin "10") (pinfunction "B_10") (pintype "input"))
      (node (ref "E1") (pin "11") (pinfunction "CLR_11") (pintype "input"))
      (node (ref "R22") (pin "1") (pinfunction "1_1") (pintype "passive"))
    )
    (net (code "38") (name "Net-(E1B-C)") (class "Default")
      (node (ref "C37") (pin "1") (pinfunction "1_1") (pintype "passive"))
      (node (ref "E1") (pin "6") (pinfunction "C_6") (pintype "input"))
    )
    (net (code "39") (name "Net-(E1B-R{slash}C)") (class "Default")
      (node (ref "C37") (pin "2") (pinfunction "2_2") (pintype "passive"))
      (node (ref "E1") (pin "7") (pinfunction "R/C_7") (pintype "input"))
      (node (ref "R7") (pin "1") (pinfunction "1_1") (pintype "passive"))
    )
    (net (code "40") (name "Net-(E2A-C)") (class "Default")
      (node (ref "C34") (pin "1") (pinfunction "1_1") (pintype "passive"))
      (node (ref "C35") (pin "1") (pinfunction "1_1") (pintype "passive"))
      (node (ref "C35A") (pin "1") (pinfunction "1_1") (pintype "passive"))
      (node (ref "E2") (pin "14") (pinfunction "C_14") (pintype "input"))
    )
    (net (code "41") (name "Net-(E2A-R{slash}C)") (class "Default")
      (node (ref "C34") (pin "2") (pinfunction "2_2") (pintype "passive"))
      (node (ref "C35") (pin "2") (pinfunction "2_2") (pintype "passive"))
      (node (ref "C35A") (pin "2") (pinfunction "2_2") (pintype "passive"))
      (node (ref "E2") (pin "15") (pinfunction "R/C_15") (pintype "input"))
      (node (ref "R19") (pin "1") (pinfunction "1_1") (pintype "passive"))
    )
    (net (code "42") (name "Net-(E2B-C)") (class "Default")
      (node (ref "C33") (pin "1") (pinfunction "1_1") (pintype "passive"))
      (node (ref "E2") (pin "6") (pinfunction "C_6") (pintype "input"))
    )
    (net (code "43") (name "Net-(E2B-R{slash}C)") (class "Default")
      (node (ref "C33") (pin "2") (pinfunction "2_2") (pintype "passive"))
      (node (ref "E2") (pin "7") (pinfunction "R/C_7") (pintype "input"))
      (node (ref "R20") (pin "1") (pinfunction "1_1") (pintype "passive"))
    )
    (net (code "44") (name "Net-(E4A-C)") (class "Default")
      (node (ref "C38") (pin "2") (pinfunction "2_2") (pintype "passive"))
      (node (ref "C39") (pin "2") (pinfunction "2_2") (pintype "passive"))
      (node (ref "E4") (pin "10") (pinfunction "C_10") (pintype "input"))
    )
    (net (code "45") (name "Net-(E5-OUT1)") (class "Default")
      (node (ref "C41") (pin "2") (pinfunction "2_2") (pintype "passive"))
      (node (ref "E5") (pin "1") (pinfunction "OUT1_1") (pintype "output"))
      (node (ref "E6") (pin "2") (pinfunction "-IN_2") (pintype "input"))
    )
    (net (code "46") (name "Net-(E5-RFB)") (class "Default")
      (node (ref "C41") (pin "1") (pinfunction "1_1") (pintype "passive"))
      (node (ref "E5") (pin "20") (pinfunction "RFB_20") (pintype "input"))
      (node (ref "E6") (pin "1") (pinfunction "OUT_1") (pintype "output"))
      (node (ref "R2") (pin "1") (pinfunction "1_1") (pintype "passive"))
    )
    (net (code "47") (name "Net-(E6B--IN)") (class "Default")
      (node (ref "E6") (pin "6") (pinfunction "-IN_6") (pintype "input"))
      (node (ref "R2") (pin "2") (pinfunction "2_2") (pintype "passive"))
      (node (ref "R3") (pin "1") (pinfunction "1_1") (pintype "passive"))
      (node (ref "R5") (pin "1") (pinfunction "1_1") (pintype "passive"))
    )
    (net (code "48") (name "Net-(E7-OUT1)") (class "Default")
      (node (ref "C42") (pin "2") (pinfunction "2_2") (pintype "passive"))
      (node (ref "E7") (pin "1") (pinfunction "OUT1_1") (pintype "output"))
      (node (ref "E8") (pin "2") (pinfunction "-IN_2") (pintype "input"))
    )
    (net (code "49") (name "Net-(E7-RFB)") (class "Default")
      (node (ref "C42") (pin "1") (pinfunction "1_1") (pintype "passive"))
      (node (ref "E7") (pin "20") (pinfunction "RFB_20") (pintype "input"))
      (node (ref "E8") (pin "1") (pinfunction "OUT_1") (pintype "output"))
      (node (ref "R6") (pin "1") (pinfunction "1_1") (pintype "passive"))
    )
    (net (code "50") (name "Net-(E8B--IN)") (class "Default")
      (node (ref "E8") (pin "6") (pinfunction "-IN_6") (pintype "input"))
      (node (ref "R11") (pin "1") (pinfunction "1_1") (pintype "passive"))
      (node (ref "R12") (pin "1") (pinfunction "1_1") (pintype "passive"))
      (node (ref "R6") (pin "2") (pinfunction "2_2") (pintype "passive"))
    )
    (net (code "51") (name "Net-(E15A-C)") (class "Default")
      (node (ref "C40") (pin "2") (pinfunction "2_2") (pintype "passive"))
      (node (ref "E15") (pin "10") (pinfunction "C_10") (pintype "input"))
    )
    (net (code "52") (name "Net-(E15A-R{slash}C)") (class "Default")
      (node (ref "C40") (pin "1") (pinfunction "1_1") (pintype "passive"))
      (node (ref "D1") (pin "C") (pinfunction "C_C") (pintype "passive"))
      (node (ref "E15") (pin "11") (pinfunction "R/C_11") (pintype "input"))
      (node (ref "R18") (pin "1") (pinfunction "1_1") (pintype "passive"))
    )
    (net (code "53") (name "Net-(Q1-B)") (class "Default")
      (node (ref "Q1") (pin "2") (pinfunction "B_2") (pintype "passive"))
      (node (ref "R14") (pin "2") (pinfunction "2_2") (pintype "passive"))
    )
    (net (code "54") (name "Net-(Q13-B)") (class "Default")
      (node (ref "Q13") (pin "2") (pinfunction "B_2") (pintype "passive"))
      (node (ref "R83") (pin "2") (pinfunction "2_2") (pintype "passive"))
    )
    (net (code "55") (name "Net-(Q13-C)") (class "Default")
      (node (ref "C64") (pin "1") (pinfunction "1_1") (pintype "passive"))
      (node (ref "Q13") (pin "3") (pinfunction "C_3") (pintype "passive"))
      (node (ref "R82") (pin "1") (pinfunction "1_1") (pintype "passive"))
    )
    (net (code "56") (name "Net-(Q13-E)") (class "Default")
      (node (ref "Q13") (pin "1") (pinfunction "E_1") (pintype "passive"))
      (node (ref "Q14") (pin "1") (pinfunction "E_1") (pintype "passive"))
      (node (ref "R86") (pin "2") (pinfunction "2_2") (pintype "passive"))
      (node (ref "R87") (pin "1") (pinfunction "1_1") (pintype "passive"))
    )
    (net (code "57") (name "Net-(Q14-B)") (class "Default")
      (node (ref "C63") (pin "2") (pinfunction "2_2") (pintype "passive"))
      (node (ref "Q14") (pin "2") (pinfunction "B_2") (pintype "passive"))
      (node (ref "Q31") (pin "3") (pinfunction "C_3") (pintype "passive"))
      (node (ref "R83") (pin "1") (pinfunction "1_1") (pintype "passive"))
      (node (ref "R84") (pin "2") (pinfunction "2_2") (pintype "passive"))
      (node (ref "W5") (pin "2") (pinfunction "2_2") (pintype "passive"))
      (node (ref "W8") (pin "2") (pinfunction "2_2") (pintype "passive"))
    )
    (net (code "58") (name "Net-(Q14-C)") (class "Default")
      (node (ref "C65") (pin "1") (pinfunction "1_1") (pintype "passive"))
      (node (ref "Q14") (pin "3") (pinfunction "C_3") (pintype "passive"))
      (node (ref "R85") (pin "2") (pinfunction "2_2") (pintype "passive"))
    )
    (net (code "59") (name "Net-(Q31-B)") (class "Default")
      (node (ref "C63") (pin "1") (pinfunction "1_1") (pintype "passive"))
      (node (ref "Q31") (pin "2") (pinfunction "B_2") (pintype "passive"))
      (node (ref "R79") (pin "2") (pinfunction "2_2") (pintype "passive"))
    )
    (net (code "60") (name "Net-(R10-Pad1)") (class "Default")
      (node (ref "R10") (pin "1") (pinfunction "1_1") (pintype "passive"))
      (node (ref "W4") (pin "2") (pinfunction "2_2") (pintype "passive"))
    )
    (net (code "61") (name "Net-(R80-Pad2)") (class "Default")
      (node (ref "R80") (pin "2") (pinfunction "2_2") (pintype "passive"))
      (node (ref "W5") (pin "1") (pinfunction "1_1") (pintype "passive"))
    )
    (net (code "62") (name "Net-(R81-Pad2)") (class "Default")
      (node (ref "R81") (pin "2") (pinfunction "2_2") (pintype "passive"))
      (node (ref "W8") (pin "1") (pinfunction "1_1") (pintype "passive"))
    )
    (net (code "63") (name "RED_DELAY") (class "Default")
      (node (ref "E2") (pin "5") (pinfunction "Q_5") (pintype "output"))
      (node (ref "E3") (pin "51") (pinfunction "IO37_51") (pintype "bidirectional"))
      (node (ref "TP1") (pin "TP") (pinfunction "TP_TP") (pintype "input"))
    )
    (net (code "64") (name "SET_DONE") (class "Default")
      (node (ref "E1") (pin "5") (pinfunction "Q_5") (pintype "output"))
      (node (ref "E3") (pin "52") (pinfunction "IO38_52") (pintype "bidirectional"))
    )
    (net (code "65") (name "TCK") (class "Default")
      (node (ref "E3") (pin "62") (pinfunction "TCK_62") (pintype "bidirectional"))
      (node (ref "ISP") (pin "1") (pinfunction "1_1") (pintype "passive"))
    )
    (net (code "66") (name "TDI") (class "Default")
      (node (ref "E3") (pin "14") (pinfunction "TDI_14") (pintype "bidirectional"))
      (node (ref "ISP") (pin "9") (pinfunction "9_9") (pintype "passive"))
    )
    (net (code "67") (name "TDO") (class "Default")
      (node (ref "E3") (pin "71") (pinfunction "TDO_71") (pintype "bidirectional"))
      (node (ref "ISP") (pin "3") (pinfunction "3_3") (pintype "passive"))
    )
    (net (code "68") (name "TMS") (class "Default")
      (node (ref "E3") (pin "23") (pinfunction "TMS_23") (pintype "bidirectional"))
      (node (ref "ISP") (pin "5") (pinfunction "5_5") (pintype "passive"))
    )
    (net (code "69") (name "TP3") (class "Default")
      (node (ref "E3") (pin "29") (pinfunction "IO20_29") (pintype "bidirectional"))
      (node (ref "OMNIBUS") (pin "CH2") (pinfunction "1_CH2") (pintype "bidirectional"))
    )
    (net (code "70") (name "VCC") (class "Default")
      (node (ref "C1") (pin "1") (pinfunction "1_1") (pintype "passive"))
      (node (ref "C13") (pin "+") (pinfunction "+_+") (pintype "passive"))
      (node (ref "C14") (pin "+") (pinfunction "+_+") (pintype "passive"))
      (node (ref "C15") (pin "+") (pinfunction "+_+") (pintype "passive"))
      (node (ref "C2") (pin "1") (pinfunction "1_1") (pintype "passive"))
      (node (ref "C3") (pin "1") (pinfunction "1_1") (pintype "passive"))
      (node (ref "C4") (pin "1") (pinfunction "1_1") (pintype "passive"))
      (node (ref "C5") (pin "1") (pinfunction "1_1") (pintype "passive"))
      (node (ref "C6") (pin "1") (pinfunction "1_1") (pintype "passive"))
      (node (ref "C7") (pin "1") (pinfunction "1_1") (pintype "passive"))
      (node (ref "C8") (pin "1") (pinfunction "1_1") (pintype "passive"))
      (node (ref "E1") (pin "2") (pinfunction "B_2") (pintype "input"))
      (node (ref "E1") (pin "3") (pinfunction "CLR_3") (pintype "input"))
      (node (ref "E15") (pin "5") (pinfunction "B_5") (pintype "input"))
      (node (ref "E2") (pin "11") (pinfunction "CLR_11") (pintype "input"))
      (node (ref "E2") (pin "2") (pinfunction "B_2") (pintype "input"))
      (node (ref "E2") (pin "3") (pinfunction "CLR_3") (pintype "input"))
      (node (ref "E4") (pin "5") (pinfunction "B_5") (pintype "input"))
      (node (ref "E5") (pin "18") (pinfunction "VDD_18") (pintype "power_in"))
      (node (ref "E7") (pin "18") (pinfunction "VDD_18") (pintype "power_in"))
      (node (ref "ISP") (pin "4") (pinfunction "4_4") (pintype "passive"))
      (node (ref "J1") (pin "SS") (pinfunction "37_SS") (pintype "bidirectional"))
      (node (ref "J1") (pin "UU") (pinfunction "39_UU") (pintype "bidirectional"))
      (node (ref "J2") (pin "SS") (pinfunction "37_SS") (pintype "bidirectional"))
      (node (ref "J2") (pin "UU") (pinfunction "39_UU") (pintype "bidirectional"))
      (node (ref "J3") (pin "1") (pinfunction "1_1") (pintype "bidirectional"))
      (node (ref "J4") (pin "1") (pinfunction "1_1") (pintype "bidirectional"))
      (node (ref "OMNIBUS") (pin "AA2") (pinfunction "1_AA2") (pintype "bidirectional"))
      (node (ref "OMNIBUS") (pin "BA2") (pinfunction "1_BA2") (pintype "bidirectional"))
      (node (ref "OMNIBUS") (pin "CA2") (pinfunction "1_CA2") (pintype "bidirectional"))
      (node (ref "OSC") (pin "8") (pinfunction "VCC_8") (pintype "power_in"))
      (node (ref "OSC1") (pin "14") (pinfunction "VCC_14") (pintype "power_in"))
      (node (ref "Q31") (pin "1") (pinfunction "E_1") (pintype "passive"))
      (node (ref "R1") (pin "2") (pinfunction "2_2") (pintype "passive"))
      (node (ref "R10") (pin "2") (pinfunction "2_2") (pintype "passive"))
      (node (ref "R15") (pin "2") (pinfunction "2_2") (pintype "passive"))
      (node (ref "R18") (pin "2") (pinfunction "2_2") (pintype "passive"))
      (node (ref "R19") (pin "2") (pinfunction "2_2") (pintype "passive"))
      (node (ref "R20") (pin "2") (pinfunction "2_2") (pintype "passive"))
      (node (ref "R22") (pin "2") (pinfunction "2_2") (pintype "passive"))
      (node (ref "R4") (pin "2") (pinfunction "2_2") (pintype "passive"))
      (node (ref "R7") (pin "2") (pinfunction "2_2") (pintype "passive"))
      (node (ref "R78") (pin "2") (pinfunction "2_2") (pintype "passive"))
      (node (ref "R8") (pin "2") (pinfunction "2_2") (pintype "passive"))
      (node (ref "R80") (pin "1") (pinfunction "1_1") (pintype "passive"))
      (node (ref "R81") (pin "1") (pinfunction "1_1") (pintype "passive"))
      (node (ref "R82") (pin "2") (pinfunction "2_2") (pintype "passive"))
      (node (ref "R9") (pin "2") (pinfunction "2_2") (pintype "passive"))
      (node (ref "RN1") (pin "1") (pinfunction "1_1") (pintype "passive"))
    )
    (net (code "71") (name "VCCINT") (class "Default")
      (node (ref "C10") (pin "1") (pinfunction "1_1") (pintype "passive"))
      (node (ref "C9") (pin "1") (pinfunction "1_1") (pintype "passive"))
      (node (ref "J4") (pin "2") (pinfunction "2_2") (pintype "bidirectional"))
    )
    (net (code "72") (name "VCCIO") (class "Default")
      (node (ref "C11") (pin "1") (pinfunction "1_1") (pintype "passive"))
      (node (ref "C12") (pin "1") (pinfunction "1_1") (pintype "passive"))
      (node (ref "J3") (pin "2") (pinfunction "2_2") (pintype "bidirectional"))
    )
    (net (code "73") (name "X_ANALOG") (class "Default")
      (node (ref "E6") (pin "7") (pinfunction "OUT_7") (pintype "output"))
      (node (ref "J1") (pin "D") (pinfunction "4_D") (pintype "bidirectional"))
      (node (ref "R5") (pin "2") (pinfunction "2_2") (pintype "passive"))
      (node (ref "X") (pin "2") (pinfunction "2_2") (pintype "passive"))
    )
    (net (code "74") (name "Y_ANALOG") (class "Default")
      (node (ref "E8") (pin "7") (pinfunction "OUT_7") (pintype "output"))
      (node (ref "J1") (pin "L") (pinfunction "10_L") (pintype "bidirectional"))
      (node (ref "R12") (pin "2") (pinfunction "2_2") (pintype "passive"))
      (node (ref "Y") (pin "2") (pinfunction "2_2") (pintype "passive"))
    )
    (net (code "75") (name "Z_AXIS") (class "Default")
      (node (ref "J1") (pin "X") (pinfunction "20_X") (pintype "bidirectional"))
      (node (ref "R87") (pin "2") (pinfunction "2_2") (pintype "passive"))
      (node (ref "Z") (pin "2") (pinfunction "2_2") (pintype "passive"))
    )
    (net (code "76") (name "unconnected-(E1A-~{Q}-Pad4)") (class "Default")
      (node (ref "E1") (pin "4") (pinfunction "~{Q}_4") (pintype "output"))
    )
    (net (code "77") (name "unconnected-(E1B-~{Q}-Pad12)") (class "Default")
      (node (ref "E1") (pin "12") (pinfunction "~{Q}_12") (pintype "output"))
    )
    (net (code "78") (name "unconnected-(E2A-~{Q}-Pad4)") (class "Default")
      (node (ref "E2") (pin "4") (pinfunction "~{Q}_4") (pintype "output"))
    )
    (net (code "79") (name "unconnected-(E2B-~{Q}-Pad12)") (class "Default")
      (node (ref "E2") (pin "12") (pinfunction "~{Q}_12") (pintype "output"))
    )
    (net (code "80") (name "unconnected-(E4A-Q-Pad6)") (class "Default")
      (node (ref "E4") (pin "6") (pinfunction "Q_6") (pintype "output"))
    )
    (net (code "81") (name "unconnected-(E4A-R-Pad9)") (class "Default")
      (node (ref "E4") (pin "9") (pinfunction "R_9") (pintype "input"))
    )
    (net (code "82") (name "unconnected-(E15A-R-Pad9)") (class "Default")
      (node (ref "E15") (pin "9") (pinfunction "R_9") (pintype "input"))
    )
    (net (code "83") (name "unconnected-(ISP-Pad6)") (class "Default")
      (node (ref "ISP") (pin "6") (pinfunction "6_6") (pintype "passive"))
    )
    (net (code "84") (name "unconnected-(ISP-Pad7)") (class "Default")
      (node (ref "ISP") (pin "7") (pinfunction "7_7") (pintype "passive"))
    )
    (net (code "85") (name "unconnected-(ISP-Pad8)") (class "Default")
      (node (ref "ISP") (pin "8") (pinfunction "8_8") (pintype "passive"))
    )
    (net (code "86") (name "unconnected-(J1-2-PadB)") (class "Default")
      (node (ref "J1") (pin "B") (pinfunction "2_B") (pintype "bidirectional"))
    )
    (net (code "87") (name "unconnected-(J1-14-PadR)") (class "Default")
      (node (ref "J1") (pin "R") (pinfunction "14_R") (pintype "bidirectional"))
    )
    (net (code "88") (name "unconnected-(J1-16-PadT)") (class "Default")
      (node (ref "J1") (pin "T") (pinfunction "16_T") (pintype "bidirectional"))
    )
    (net (code "89") (name "unconnected-(J1-36-PadRR)") (class "Default")
      (node (ref "J1") (pin "RR") (pinfunction "36_RR") (pintype "bidirectional"))
    )
    (net (code "90") (name "unconnected-(J1-38-PadTT)") (class "Default")
      (node (ref "J1") (pin "TT") (pinfunction "38_TT") (pintype "bidirectional"))
    )
    (net (code "91") (name "unconnected-(J1-40-PadVV)") (class "Default")
      (node (ref "J1") (pin "VV") (pinfunction "40_VV") (pintype "bidirectional"))
    )
    (net (code "92") (name "unconnected-(J2-10-PadL)") (class "Default")
      (node (ref "J2") (pin "L") (pinfunction "10_L") (pintype "bidirectional"))
    )
    (net (code "93") (name "unconnected-(J2-12-PadN)") (class "Default")
      (node (ref "J2") (pin "N") (pinfunction "12_N") (pintype "bidirectional"))
    )
    (net (code "94") (name "unconnected-(J2-14-PadR)") (class "Default")
      (node (ref "J2") (pin "R") (pinfunction "14_R") (pintype "bidirectional"))
    )
    (net (code "95") (name "unconnected-(J2-16-PadT)") (class "Default")
      (node (ref "J2") (pin "T") (pinfunction "16_T") (pintype "bidirectional"))
    )
    (net (code "96") (name "unconnected-(J2-26-PadDD)") (class "Default")
      (node (ref "J2") (pin "DD") (pinfunction "26_DD") (pintype "bidirectional"))
    )
    (net (code "97") (name "unconnected-(J2-28-PadFF)") (class "Default")
      (node (ref "J2") (pin "FF") (pinfunction "28_FF") (pintype "bidirectional"))
    )
    (net (code "98") (name "unconnected-(J2-30-PadJJ)") (class "Default")
      (node (ref "J2") (pin "JJ") (pinfunction "30_JJ") (pintype "bidirectional"))
    )
    (net (code "99") (name "unconnected-(J2-32-PadLL)") (class "Default")
      (node (ref "J2") (pin "LL") (pinfunction "32_LL") (pintype "bidirectional"))
    )
    (net (code "100") (name "unconnected-(J2-34-PadNN)") (class "Default")
      (node (ref "J2") (pin "NN") (pinfunction "34_NN") (pintype "bidirectional"))
    )
    (net (code "101") (name "unconnected-(J2-36-PadRR)") (class "Default")
      (node (ref "J2") (pin "RR") (pinfunction "36_RR") (pintype "bidirectional"))
    )
    (net (code "102") (name "unconnected-(J2-38-PadTT)") (class "Default")
      (node (ref "J2") (pin "TT") (pinfunction "38_TT") (pintype "bidirectional"))
    )
    (net (code "103") (name "unconnected-(J2-40-PadVV)") (class "Default")
      (node (ref "J2") (pin "VV") (pinfunction "40_VV") (pintype "bidirectional"))
    )
    (net (code "104") (name "~{B_DIXY}") (class "Default")
      (node (ref "E15") (pin "3") (pinfunction "A1_3") (pintype "input"))
      (node (ref "E15") (pin "4") (pinfunction "A2_4") (pintype "input"))
      (node (ref "E3") (pin "55") (pinfunction "IO40_55") (pintype "bidirectional"))
    )
    (net (code "105") (name "~{C0}") (class "Default")
      (node (ref "E3") (pin "31") (pinfunction "IO22_31") (pintype "bidirectional"))
      (node (ref "OMNIBUS") (pin "CE1") (pinfunction "1_CE1") (pintype "bidirectional"))
    )
    (net (code "106") (name "~{C1}") (class "Default")
      (node (ref "E3") (pin "30") (pinfunction "IO21_30") (pintype "bidirectional"))
      (node (ref "OMNIBUS") (pin "CH1") (pinfunction "1_CH1") (pintype "bidirectional"))
    )
    (net (code "107") (name "~{CHAN}") (class "Default")
      (node (ref "E3") (pin "57") (pinfunction "IO42_57") (pintype "bidirectional"))
      (node (ref "J1") (pin "Z") (pinfunction "22_Z") (pintype "bidirectional"))
    )
    (net (code "108") (name "~{COL_RED}") (class "Default")
      (node (ref "E3") (pin "56") (pinfunction "IO41_56") (pintype "bidirectional"))
      (node (ref "J1") (pin "DD") (pinfunction "26_DD") (pintype "bidirectional"))
    )
    (net (code "109") (name "~{DATA0}") (class "Default")
      (node (ref "E3") (pin "49") (pinfunction "IO35_49") (pintype "bidirectional"))
      (node (ref "OMNIBUS") (pin "AR1") (pinfunction "1_AR1") (pintype "bidirectional"))
    )
    (net (code "110") (name "~{DATA1}") (class "Default")
      (node (ref "E3") (pin "48") (pinfunction "IO34_48") (pintype "bidirectional"))
      (node (ref "OMNIBUS") (pin "AS1") (pinfunction "1_AS1") (pintype "bidirectional"))
    )
    (net (code "111") (name "~{DATA2}") (class "Default")
      (node (ref "E3") (pin "46") (pinfunction "IO33_46") (pintype "bidirectional"))
      (node (ref "OMNIBUS") (pin "AU1") (pinfunction "1_AU1") (pintype "bidirectional"))
    )
    (net (code "112") (name "~{DATA3}") (class "Default")
      (node (ref "E3") (pin "45") (pinfunction "IO/PD2_45") (pintype "bidirectional"))
      (node (ref "OMNIBUS") (pin "AV1") (pinfunction "1_AV1") (pintype "bidirectional"))
    )
    (net (code "113") (name "~{DATA4}") (class "Default")
      (node (ref "E3") (pin "37") (pinfunction "IO27_37") (pintype "bidirectional"))
      (node (ref "OMNIBUS") (pin "BR1") (pinfunction "1_BR1") (pintype "bidirectional"))
    )
    (net (code "114") (name "~{DATA5}") (class "Default")
      (node (ref "E3") (pin "36") (pinfunction "IO26_36") (pintype "bidirectional"))
      (node (ref "OMNIBUS") (pin "BS1") (pinfunction "1_BS1") (pintype "bidirectional"))
    )
    (net (code "115") (name "~{DATA6}") (class "Default")
      (node (ref "E3") (pin "35") (pinfunction "IO25_35") (pintype "bidirectional"))
      (node (ref "OMNIBUS") (pin "BU1") (pinfunction "1_BU1") (pintype "bidirectional"))
    )
    (net (code "116") (name "~{DATA7}") (class "Default")
      (node (ref "E3") (pin "34") (pinfunction "IO24_34") (pintype "bidirectional"))
      (node (ref "OMNIBUS") (pin "BV1") (pinfunction "1_BV1") (pintype "bidirectional"))
    )
    (net (code "117") (name "~{DATA8}") (class "Default")
      (node (ref "E3") (pin "17") (pinfunction "IO11_17") (pintype "bidirectional"))
      (node (ref "OMNIBUS") (pin "DR1") (pinfunction "1_DR1") (pintype "bidirectional"))
    )
    (net (code "118") (name "~{DATA9}") (class "Default")
      (node (ref "E3") (pin "16") (pinfunction "IO10_16") (pintype "bidirectional"))
      (node (ref "OMNIBUS") (pin "DS1") (pinfunction "1_DS1") (pintype "bidirectional"))
    )
    (net (code "119") (name "~{DATA10}") (class "Default")
      (node (ref "E3") (pin "15") (pinfunction "IO9_15") (pintype "bidirectional"))
      (node (ref "OMNIBUS") (pin "DU1") (pinfunction "1_DU1") (pintype "bidirectional"))
    )
    (net (code "120") (name "~{DATA11}") (class "Default")
      (node (ref "E3") (pin "12") (pinfunction "IO/PD1_12") (pintype "bidirectional"))
      (node (ref "OMNIBUS") (pin "DV1") (pinfunction "1_DV1") (pintype "bidirectional"))
    )
    (net (code "121") (name "~{DEL_1}") (class "Default")
      (node (ref "E15") (pin "1") (pinfunction "~{Q}_1") (pintype "output"))
      (node (ref "E3") (pin "84") (pinfunction "IN/OE1_84") (pintype "input"))
      (node (ref "S1") (pin "1") (pinfunction "O_1") (pintype "passive"))
    )
    (net (code "122") (name "~{DI02}") (class "Default")
      (node (ref "E3") (pin "64") (pinfunction "IO47_64") (pintype "bidirectional"))
      (node (ref "E5") (pin "4") (pinfunction "DB11_4") (pintype "input"))
      (node (ref "E7") (pin "4") (pinfunction "DB11_4") (pintype "input"))
    )
    (net (code "123") (name "~{DLY_DONE}") (class "Default")
      (node (ref "E1") (pin "1") (pinfunction "A_1") (pintype "input"))
      (node (ref "E3") (pin "63") (pinfunction "IO46_63") (pintype "bidirectional"))
    )
    (net (code "124") (name "~{ERASE_INTERVAL}") (class "Default")
      (node (ref "J1") (pin "NN") (pinfunction "34_NN") (pintype "bidirectional"))
      (node (ref "R14") (pin "1") (pinfunction "1_1") (pintype "passive"))
    )
    (net (code "125") (name "~{ERASE}") (class "Default")
      (node (ref "E3") (pin "58") (pinfunction "IO43_58") (pintype "bidirectional"))
      (node (ref "J1") (pin "FF") (pinfunction "28_FF") (pintype "bidirectional"))
    )
    (net (code "126") (name "~{INTERNAL_IO}") (class "Default")
      (node (ref "E3") (pin "28") (pinfunction "IO19_28") (pintype "bidirectional"))
      (node (ref "OMNIBUS") (pin "CL1") (pinfunction "1_CL1") (pintype "bidirectional"))
    )
    (net (code "127") (name "~{INTERRUPT}") (class "Default")
      (node (ref "E3") (pin "27") (pinfunction "IO18_27") (pintype "bidirectional"))
      (node (ref "OMNIBUS") (pin "CP1") (pinfunction "1_CP1") (pintype "bidirectional"))
    )
    (net (code "128") (name "~{LD_DEL}") (class "Default")
      (node (ref "E3") (pin "81") (pinfunction "IO/GCLK3_81") (pintype "bidirectional"))
      (node (ref "E4") (pin "1") (pinfunction "~{Q}_1") (pintype "output"))
    )
    (net (code "129") (name "~{LOAD_X}") (class "Default")
      (node (ref "E3") (pin "77") (pinfunction "IO57_77") (pintype "bidirectional"))
      (node (ref "E4") (pin "3") (pinfunction "A1_3") (pintype "input"))
      (node (ref "E5") (pin "16") (pinfunction "CS_16") (pintype "input"))
      (node (ref "E5") (pin "17") (pinfunction "WR_17") (pintype "input"))
    )
    (net (code "130") (name "~{LOAD_Y}") (class "Default")
      (node (ref "E3") (pin "79") (pinfunction "IO58_79") (pintype "bidirectional"))
      (node (ref "E4") (pin "4") (pinfunction "A2_4") (pintype "input"))
      (node (ref "E7") (pin "16") (pinfunction "CS_16") (pintype "input"))
      (node (ref "E7") (pin "17") (pinfunction "WR_17") (pintype "input"))
    )
    (net (code "131") (name "~{MD3}") (class "Default")
      (node (ref "E3") (pin "50") (pinfunction "IO36_50") (pintype "bidirectional"))
      (node (ref "OMNIBUS") (pin "AP1") (pinfunction "1_AP1") (pintype "bidirectional"))
    )
    (net (code "132") (name "~{MD4}") (class "Default")
      (node (ref "E3") (pin "44") (pinfunction "IO31_44") (pintype "bidirectional"))
      (node (ref "OMNIBUS") (pin "BK1") (pinfunction "1_BK1") (pintype "bidirectional"))
    )
    (net (code "133") (name "~{MD5}") (class "Default")
      (node (ref "E3") (pin "41") (pinfunction "IO30_41") (pintype "bidirectional"))
      (node (ref "OMNIBUS") (pin "BL1") (pinfunction "1_BL1") (pintype "bidirectional"))
    )
    (net (code "134") (name "~{MD6}") (class "Default")
      (node (ref "E3") (pin "40") (pinfunction "IO29_40") (pintype "bidirectional"))
      (node (ref "OMNIBUS") (pin "BM1") (pinfunction "1_BM1") (pintype "bidirectional"))
    )
    (net (code "135") (name "~{MD7}") (class "Default")
      (node (ref "E3") (pin "39") (pinfunction "IO28_39") (pintype "bidirectional"))
      (node (ref "OMNIBUS") (pin "BP1") (pinfunction "1_BP1") (pintype "bidirectional"))
    )
    (net (code "136") (name "~{MD8}") (class "Default")
      (node (ref "E3") (pin "22") (pinfunction "IO15_22") (pintype "bidirectional"))
      (node (ref "OMNIBUS") (pin "DK1") (pinfunction "1_DK1") (pintype "bidirectional"))
    )
    (net (code "137") (name "~{MD9}") (class "Default")
      (node (ref "E3") (pin "21") (pinfunction "IO14_21") (pintype "bidirectional"))
      (node (ref "OMNIBUS") (pin "DL1") (pinfunction "1_DL1") (pintype "bidirectional"))
    )
    (net (code "138") (name "~{MD10}") (class "Default")
      (node (ref "E3") (pin "20") (pinfunction "IO13_20") (pintype "bidirectional"))
      (node (ref "OMNIBUS") (pin "DM1") (pinfunction "1_DM1") (pintype "bidirectional"))
    )
    (net (code "139") (name "~{MD11}") (class "Default")
      (node (ref "E3") (pin "18") (pinfunction "IO12_18") (pintype "bidirectional"))
      (node (ref "OMNIBUS") (pin "DP1") (pinfunction "1_DP1") (pintype "bidirectional"))
    )
    (net (code "140") (name "~{NON_STORE}") (class "Default")
      (node (ref "E3") (pin "80") (pinfunction "IO59_80") (pintype "bidirectional"))
      (node (ref "J1") (pin "LL") (pinfunction "32_LL") (pintype "bidirectional"))
    )
    (net (code "141") (name "~{PAUSE}") (class "Default")
      (node (ref "E3") (pin "33") (pinfunction "IO23_33") (pintype "bidirectional"))
      (node (ref "OMNIBUS") (pin "CD1") (pinfunction "1_CD1") (pintype "bidirectional"))
    )
    (net (code "142") (name "~{SKIP}") (class "Default")
      (node (ref "E3") (pin "24") (pinfunction "IO16_24") (pintype "bidirectional"))
      (node (ref "OMNIBUS") (pin "CS1") (pinfunction "1_CS1") (pintype "bidirectional"))
    )
    (net (code "143") (name "~{WRITE_THRU}") (class "Default")
      (node (ref "E3") (pin "60") (pinfunction "IO44_60") (pintype "bidirectional"))
      (node (ref "J1") (pin "JJ") (pinfunction "30_JJ") (pintype "bidirectional"))
    )
  )
)
